# battery-board.net
KiCad netlist of a schematic drawn in EAGLE
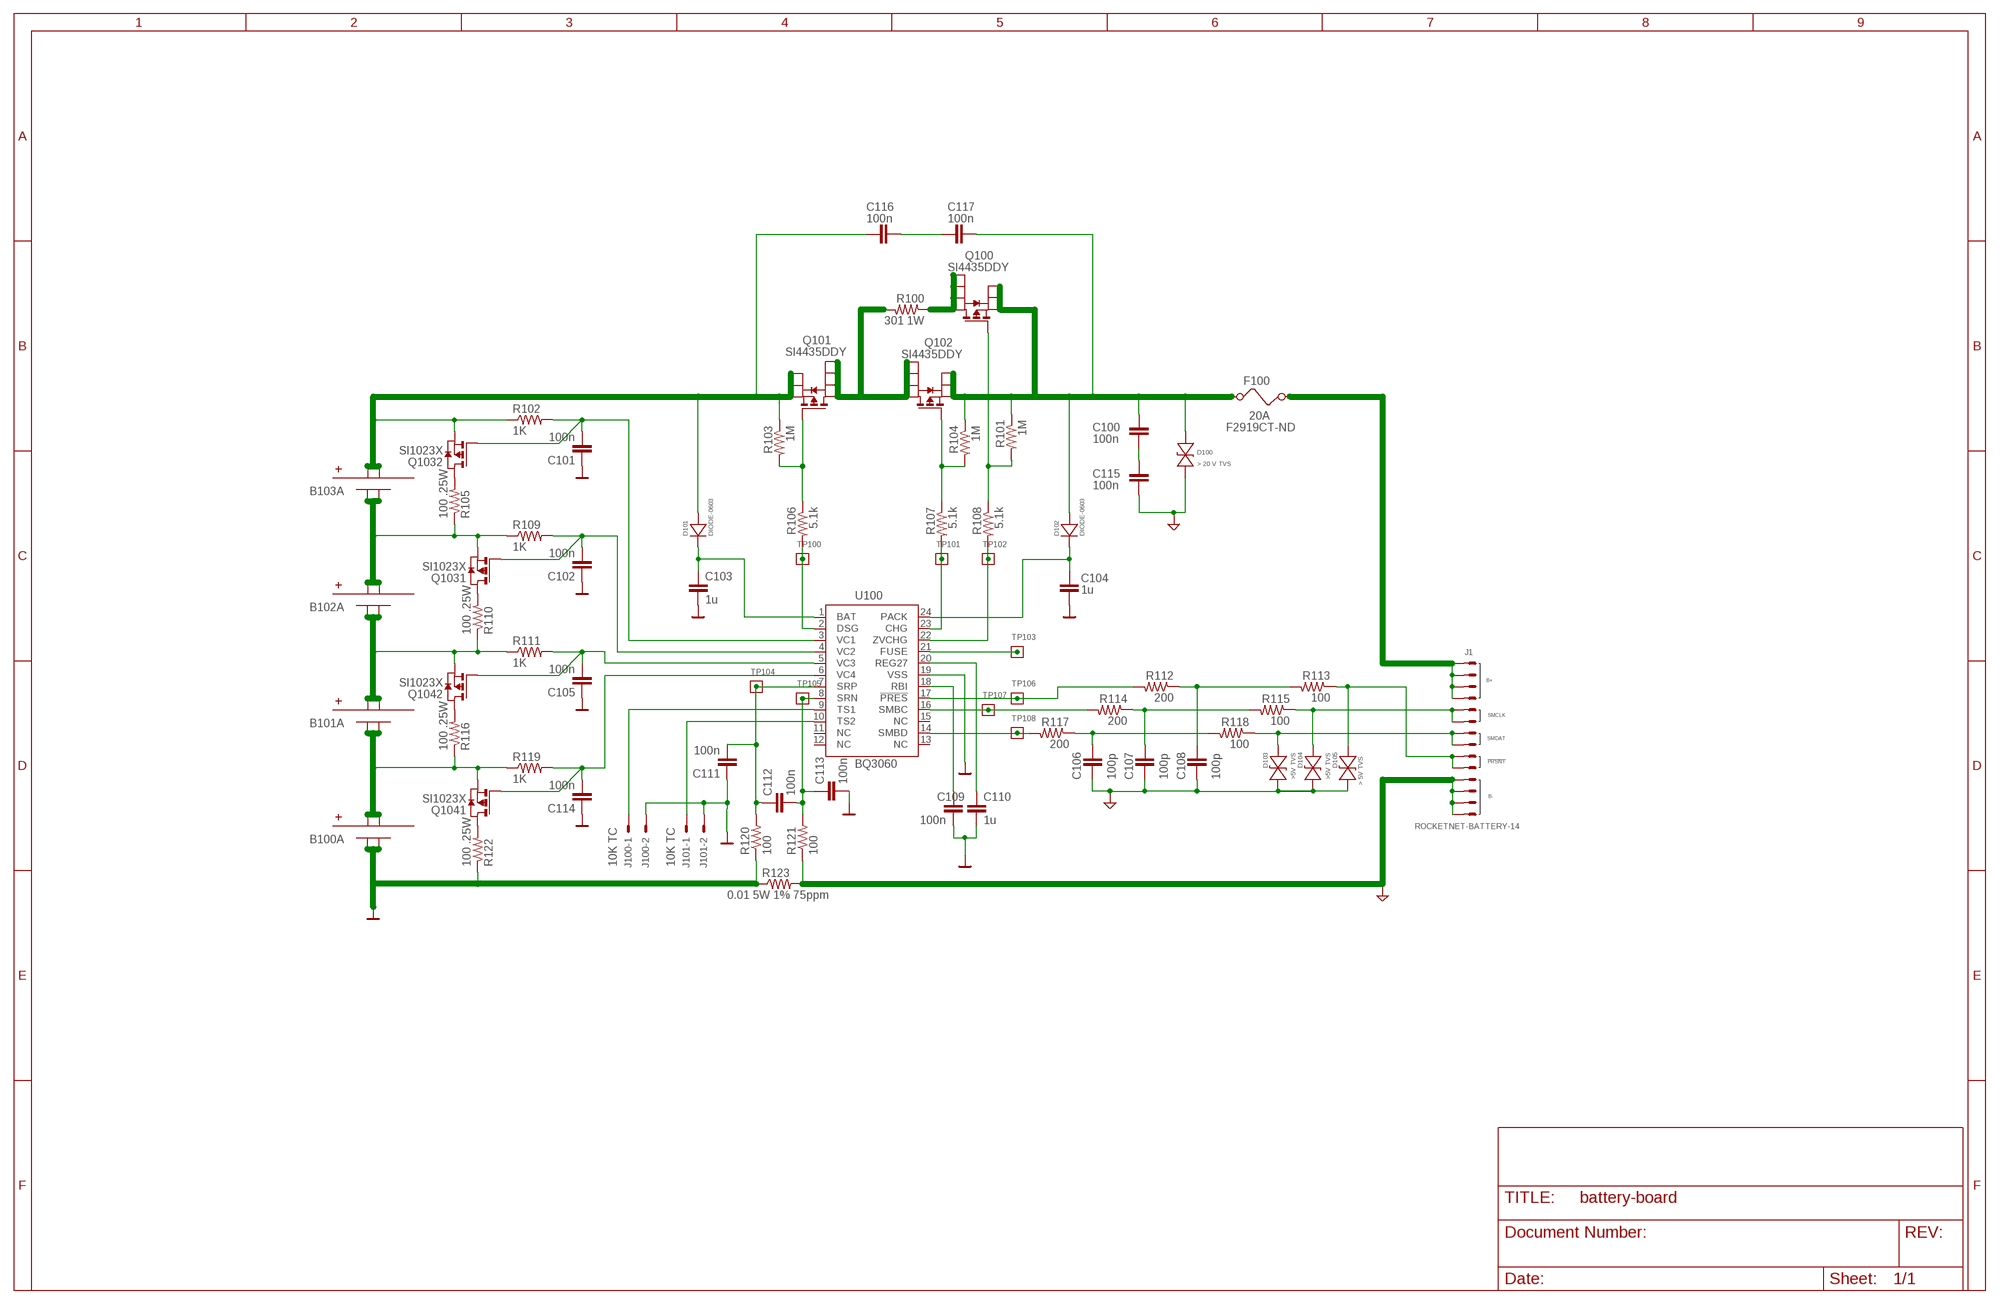
[diagram p0: schematic, sheet 1]

(export (version "E")
  (design (tool "Eeschema 10.0.6"))
  (components
    (comp (ref "B100A")
      (value "LIPO-8AHR")
      (footprint "eagle-import:LIPO-8AHR-PAC")
      (libsource (lib "eagle-import") (part "LIPO-8AHR"))
    )
    (comp (ref "B101A")
      (value "LIPO-8AHR")
      (footprint "eagle-import:LIPO-8AHR-PAC")
      (libsource (lib "eagle-import") (part "LIPO-8AHR"))
    )
    (comp (ref "B102A")
      (value "LIPO-8AHR")
      (footprint "eagle-import:LIPO-8AHR-PAC")
      (libsource (lib "eagle-import") (part "LIPO-8AHR"))
    )
    (comp (ref "B103A")
      (value "LIPO-8AHR")
      (footprint "eagle-import:LIPO-8AHR-PAC")
      (libsource (lib "eagle-import") (part "LIPO-8AHR"))
    )
    (comp (ref "C100")
      (value "100n")
      (footprint "eagle-import:0603-B-NOSILK")
      (libsource (lib "eagle-import") (part "C-EU0603-B-NOSILK"))
    )
    (comp (ref "C101")
      (value "100n")
      (footprint "eagle-import:0402-B-NOSILK")
      (libsource (lib "eagle-import") (part "C-EU0402-B-NOSILK"))
    )
    (comp (ref "C102")
      (value "100n")
      (footprint "eagle-import:0402-B-NOSILK")
      (libsource (lib "eagle-import") (part "C-EU0402-B-NOSILK"))
    )
    (comp (ref "C103")
      (value "1u")
      (footprint "eagle-import:0603-B-NOSILK")
      (libsource (lib "eagle-import") (part "C-EU0603-B-NOSILK"))
    )
    (comp (ref "C104")
      (value "1u")
      (footprint "eagle-import:0603-B-NOSILK")
      (libsource (lib "eagle-import") (part "C-EU0603-B-NOSILK"))
    )
    (comp (ref "C105")
      (value "100n")
      (footprint "eagle-import:0402-B-NOSILK")
      (libsource (lib "eagle-import") (part "C-EU0402-B-NOSILK"))
    )
    (comp (ref "C106")
      (value "100p")
      (footprint "eagle-import:0603-B-NOSILK")
      (libsource (lib "eagle-import") (part "C-EU0603-B-NOSILK"))
    )
    (comp (ref "C107")
      (value "100p")
      (footprint "eagle-import:0603-B-NOSILK")
      (libsource (lib "eagle-import") (part "C-EU0603-B-NOSILK"))
    )
    (comp (ref "C108")
      (value "100p")
      (footprint "eagle-import:0603-B-NOSILK")
      (libsource (lib "eagle-import") (part "C-EU0603-B-NOSILK"))
    )
    (comp (ref "C109")
      (value "100n")
      (footprint "eagle-import:0402-B-NOSILK")
      (libsource (lib "eagle-import") (part "C-EU0402-B-NOSILK"))
    )
    (comp (ref "C110")
      (value "1u")
      (footprint "eagle-import:0603-B-NOSILK")
      (libsource (lib "eagle-import") (part "C-EU0603-B-NOSILK"))
    )
    (comp (ref "C111")
      (value "100n")
      (footprint "eagle-import:0402-B-NOSILK")
      (libsource (lib "eagle-import") (part "C-EU0402-B-NOSILK"))
    )
    (comp (ref "C112")
      (value "100n")
      (footprint "eagle-import:0402-B-NOSILK")
      (libsource (lib "eagle-import") (part "C-EU0402-B-NOSILK"))
    )
    (comp (ref "C113")
      (value "100n")
      (footprint "eagle-import:0402-B-NOSILK")
      (libsource (lib "eagle-import") (part "C-EU0402-B-NOSILK"))
    )
    (comp (ref "C114")
      (value "100n")
      (footprint "eagle-import:0402-B-NOSILK")
      (libsource (lib "eagle-import") (part "C-EU0402-B-NOSILK"))
    )
    (comp (ref "C115")
      (value "100n")
      (footprint "eagle-import:0603-B-NOSILK")
      (libsource (lib "eagle-import") (part "C-EU0603-B-NOSILK"))
    )
    (comp (ref "C116")
      (value "100n")
      (footprint "eagle-import:0603-B-NOSILK")
      (libsource (lib "eagle-import") (part "C-EU0603-B-NOSILK"))
    )
    (comp (ref "C117")
      (value "100n")
      (footprint "eagle-import:0603-B-NOSILK")
      (libsource (lib "eagle-import") (part "C-EU0603-B-NOSILK"))
    )
    (comp (ref "D100")
      (value "> 20 V TVS")
      (footprint "eagle-import:0603-B-NOSILK-DIODE")
      (libsource (lib "eagle-import") (part "TVS-0603"))
    )
    (comp (ref "D101")
      (value "DIODE-0603")
      (footprint "eagle-import:0603-B-NOSILK-DIODE")
      (libsource (lib "eagle-import") (part "DIODE-0603"))
    )
    (comp (ref "D102")
      (value "DIODE-0603")
      (footprint "eagle-import:0603-B-NOSILK-DIODE")
      (libsource (lib "eagle-import") (part "DIODE-0603"))
    )
    (comp (ref "D103")
      (value ">5V TVS")
      (footprint "eagle-import:0603-B-NOSILK-DIODE")
      (libsource (lib "eagle-import") (part "TVS-0603"))
    )
    (comp (ref "D104")
      (value ">5V TVS")
      (footprint "eagle-import:0603-B-NOSILK-DIODE")
      (libsource (lib "eagle-import") (part "TVS-0603"))
    )
    (comp (ref "D105")
      (value "> 5V TVS")
      (footprint "eagle-import:0603-B-NOSILK-DIODE")
      (libsource (lib "eagle-import") (part "TVS-0603"))
    )
    (comp (ref "F100")
      (value "20A")
      (footprint "eagle-import:1206")
      (fields (field (name "DK") "F2919CT-ND"))
      (libsource (lib "eagle-import") (part "FUSE1206"))
    )
    (comp (ref "J1")
      (value "ROCKETNET-BATTERY-14")
      (footprint "eagle-import:ROCKETNET-CONNECTOR-M-14")
      (libsource (lib "eagle-import") (part "ROCKETNET-BATTERY-14"))
    )
    (comp (ref "J100")
      (value "87758-0216")
      (footprint "eagle-import:87758-0216")
      (libsource (lib "eagle-import") (part "87758-0216"))
    )
    (comp (ref "J101")
      (value "87758-0216")
      (footprint "eagle-import:87758-0216")
      (libsource (lib "eagle-import") (part "87758-0216"))
    )
    (comp (ref "Q100")
      (value "SI4435DDY")
      (footprint "eagle-import:SO-8")
      (libsource (lib "eagle-import") (part "SI4435DDY"))
    )
    (comp (ref "Q101")
      (value "SI4435DDY")
      (footprint "eagle-import:SO-8")
      (libsource (lib "eagle-import") (part "SI4435DDY"))
    )
    (comp (ref "Q102")
      (value "SI4435DDY")
      (footprint "eagle-import:SO-8")
      (libsource (lib "eagle-import") (part "SI4435DDY"))
    )
    (comp (ref "Q103")
      (value "SI1023X")
      (footprint "eagle-import:SOT-563")
      (libsource (lib "eagle-import") (part "SI1023X"))
    )
    (comp (ref "Q104")
      (value "SI1023X")
      (footprint "eagle-import:SOT-563")
      (libsource (lib "eagle-import") (part "SI1023X"))
    )
    (comp (ref "R100")
      (value "301 1W")
      (footprint "eagle-import:1206-B")
      (libsource (lib "eagle-import") (part "R-US_1206-B"))
    )
    (comp (ref "R101")
      (value "1M")
      (footprint "eagle-import:0402-B-NOSILK")
      (libsource (lib "eagle-import") (part "R-US_0402-B-NOSILK"))
    )
    (comp (ref "R102")
      (value "1K")
      (footprint "eagle-import:0402-B-NOSILK")
      (libsource (lib "eagle-import") (part "R-US_0402-B-NOSILK"))
    )
    (comp (ref "R103")
      (value "1M")
      (footprint "eagle-import:0402-B-NOSILK")
      (libsource (lib "eagle-import") (part "R-US_0402-B-NOSILK"))
    )
    (comp (ref "R104")
      (value "1M")
      (footprint "eagle-import:0402-B-NOSILK")
      (libsource (lib "eagle-import") (part "R-US_0402-B-NOSILK"))
    )
    (comp (ref "R105")
      (value "100 .25W")
      (footprint "eagle-import:0603-B-NOSILK")
      (libsource (lib "eagle-import") (part "R-US_0603-B-NOSILK"))
    )
    (comp (ref "R106")
      (value "5.1k")
      (footprint "eagle-import:0402-B-NOSILK")
      (libsource (lib "eagle-import") (part "R-US_0402-B-NOSILK"))
    )
    (comp (ref "R107")
      (value "5.1k")
      (footprint "eagle-import:0402-B-NOSILK")
      (libsource (lib "eagle-import") (part "R-US_0402-B-NOSILK"))
    )
    (comp (ref "R108")
      (value "5.1k")
      (footprint "eagle-import:0402-B-NOSILK")
      (libsource (lib "eagle-import") (part "R-US_0402-B-NOSILK"))
    )
    (comp (ref "R109")
      (value "1K")
      (footprint "eagle-import:0402-B-NOSILK")
      (libsource (lib "eagle-import") (part "R-US_0402-B-NOSILK"))
    )
    (comp (ref "R110")
      (value "100 .25W")
      (footprint "eagle-import:0603-B-NOSILK")
      (libsource (lib "eagle-import") (part "R-US_0603-B-NOSILK"))
    )
    (comp (ref "R111")
      (value "1K")
      (footprint "eagle-import:0402-B-NOSILK")
      (libsource (lib "eagle-import") (part "R-US_0402-B-NOSILK"))
    )
    (comp (ref "R112")
      (value "200")
      (footprint "eagle-import:0603-B-NOSILK")
      (libsource (lib "eagle-import") (part "R-US_0603-B-NOSILK"))
    )
    (comp (ref "R113")
      (value "100")
      (footprint "eagle-import:0603-B-NOSILK")
      (libsource (lib "eagle-import") (part "R-US_0603-B-NOSILK"))
    )
    (comp (ref "R114")
      (value "200")
      (footprint "eagle-import:0603-B-NOSILK")
      (libsource (lib "eagle-import") (part "R-US_0603-B-NOSILK"))
    )
    (comp (ref "R115")
      (value "100")
      (footprint "eagle-import:0603-B-NOSILK")
      (libsource (lib "eagle-import") (part "R-US_0603-B-NOSILK"))
    )
    (comp (ref "R116")
      (value "100 .25W")
      (footprint "eagle-import:0603-B-NOSILK")
      (libsource (lib "eagle-import") (part "R-US_0603-B-NOSILK"))
    )
    (comp (ref "R117")
      (value "200")
      (footprint "eagle-import:0603-B-NOSILK")
      (libsource (lib "eagle-import") (part "R-US_0603-B-NOSILK"))
    )
    (comp (ref "R118")
      (value "100")
      (footprint "eagle-import:0603-B-NOSILK")
      (libsource (lib "eagle-import") (part "R-US_0603-B-NOSILK"))
    )
    (comp (ref "R119")
      (value "1K")
      (footprint "eagle-import:0402-B-NOSILK")
      (libsource (lib "eagle-import") (part "R-US_0402-B-NOSILK"))
    )
    (comp (ref "R120")
      (value "100")
      (footprint "eagle-import:0402-B-NOSILK")
      (libsource (lib "eagle-import") (part "R-US_0402-B-NOSILK"))
    )
    (comp (ref "R121")
      (value "100")
      (footprint "eagle-import:0402-B-NOSILK")
      (libsource (lib "eagle-import") (part "R-US_0402-B-NOSILK"))
    )
    (comp (ref "R122")
      (value "100 .25W")
      (footprint "eagle-import:0603-B-NOSILK")
      (libsource (lib "eagle-import") (part "R-US_0603-B-NOSILK"))
    )
    (comp (ref "R123")
      (value "0.01 5W 1% 75ppm")
      (footprint "eagle-import:VISHAY-2818")
      (libsource (lib "eagle-import") (part "R-US-2818"))
    )
    (comp (ref "TP100")
      (value "TEST-POINT")
      (footprint "eagle-import:2MM-TEST-POINT")
      (libsource (lib "eagle-import") (part "TEST-POINT"))
    )
    (comp (ref "TP101")
      (value "TEST-POINT")
      (footprint "eagle-import:2MM-TEST-POINT")
      (libsource (lib "eagle-import") (part "TEST-POINT"))
    )
    (comp (ref "TP102")
      (value "TEST-POINT")
      (footprint "eagle-import:2MM-TEST-POINT")
      (libsource (lib "eagle-import") (part "TEST-POINT"))
    )
    (comp (ref "TP103")
      (value "TEST-POINT")
      (footprint "eagle-import:2MM-TEST-POINT")
      (libsource (lib "eagle-import") (part "TEST-POINT"))
    )
    (comp (ref "TP104")
      (value "TEST-POINT")
      (footprint "eagle-import:2MM-TEST-POINT")
      (libsource (lib "eagle-import") (part "TEST-POINT"))
    )
    (comp (ref "TP105")
      (value "TEST-POINT")
      (footprint "eagle-import:2MM-TEST-POINT")
      (libsource (lib "eagle-import") (part "TEST-POINT"))
    )
    (comp (ref "TP106")
      (value "TEST-POINT")
      (footprint "eagle-import:2MM-TEST-POINT")
      (libsource (lib "eagle-import") (part "TEST-POINT"))
    )
    (comp (ref "TP107")
      (value "TEST-POINT")
      (footprint "eagle-import:2MM-TEST-POINT")
      (libsource (lib "eagle-import") (part "TEST-POINT"))
    )
    (comp (ref "TP108")
      (value "TEST-POINT")
      (footprint "eagle-import:2MM-TEST-POINT")
      (libsource (lib "eagle-import") (part "TEST-POINT"))
    )
    (comp (ref "U100")
      (value "BQ3060PW")
      (footprint "eagle-import:PW-R-PDSO-G24")
      (libsource (lib "eagle-import") (part "BQ3060PW"))
    )
  )
  (nets
    (net (code "1") (name "Net-(C100-Pad1)") (class "Default")
      (node (ref "C100") (pin "1") (pinfunction "1_1") (pintype "passive"))
      (node (ref "C117") (pin "2") (pinfunction "2_2") (pintype "passive"))
      (node (ref "D100") (pin "ANODE") (pinfunction "ANODE_ANODE") (pintype "passive"))
      (node (ref "D102") (pin "ANODE") (pinfunction "ANODE_ANODE") (pintype "passive"))
      (node (ref "F100") (pin "1") (pinfunction "1_1") (pintype "passive"))
      (node (ref "Q100") (pin "1") (pinfunction "S_1") (pintype "passive"))
      (node (ref "Q100") (pin "2") (pinfunction "S_2") (pintype "passive"))
      (node (ref "Q100") (pin "3") (pinfunction "S_3") (pintype "passive"))
      (node (ref "Q102") (pin "1") (pinfunction "S_1") (pintype "passive"))
      (node (ref "Q102") (pin "2") (pinfunction "S_2") (pintype "passive"))
      (node (ref "Q102") (pin "3") (pinfunction "S_3") (pintype "passive"))
      (node (ref "R101") (pin "1") (pinfunction "1_1") (pintype "passive"))
      (node (ref "R104") (pin "1") (pinfunction "1_1") (pintype "passive"))
    )
    (net (code "2") (name "Net-(C100-Pad2)") (class "Default")
      (node (ref "C100") (pin "2") (pinfunction "2_2") (pintype "passive"))
      (node (ref "C115") (pin "1") (pinfunction "1_1") (pintype "passive"))
    )
    (net (code "3") (name "Net-(C106-Pad1)") (class "Default")
      (node (ref "C106") (pin "1") (pinfunction "1_1") (pintype "passive"))
      (node (ref "R117") (pin "1") (pinfunction "1_1") (pintype "passive"))
      (node (ref "R118") (pin "2") (pinfunction "2_2") (pintype "passive"))
    )
    (net (code "4") (name "Net-(C107-Pad1)") (class "Default")
      (node (ref "C107") (pin "1") (pinfunction "1_1") (pintype "passive"))
      (node (ref "R114") (pin "1") (pinfunction "1_1") (pintype "passive"))
      (node (ref "R115") (pin "2") (pinfunction "2_2") (pintype "passive"))
    )
    (net (code "5") (name "Net-(C108-Pad1)") (class "Default")
      (node (ref "C108") (pin "1") (pinfunction "1_1") (pintype "passive"))
      (node (ref "R112") (pin "1") (pinfunction "1_1") (pintype "passive"))
      (node (ref "R113") (pin "2") (pinfunction "2_2") (pintype "passive"))
    )
    (net (code "6") (name "Net-(C116-Pad2)") (class "Default")
      (node (ref "C116") (pin "2") (pinfunction "2_2") (pintype "passive"))
      (node (ref "C117") (pin "1") (pinfunction "1_1") (pintype "passive"))
    )
    (net (code "7") (name "Net-(D103-PadANODE)") (class "Default")
      (node (ref "D103") (pin "ANODE") (pinfunction "ANODE_ANODE") (pintype "passive"))
      (node (ref "J1") (pin "SMDAT@7") (pinfunction "SMDAT_SMDAT@7") (pintype "passive"))
      (node (ref "J1") (pin "SMDAT@8") (pinfunction "SMDAT_SMDAT@8") (pintype "passive"))
      (node (ref "R118") (pin "1") (pinfunction "1_1") (pintype "passive"))
    )
    (net (code "8") (name "Net-(D104-PadANODE)") (class "Default")
      (node (ref "D104") (pin "ANODE") (pinfunction "ANODE_ANODE") (pintype "passive"))
      (node (ref "J1") (pin "SMCLK@3") (pinfunction "SMCLK_SMCLK@3") (pintype "passive"))
      (node (ref "J1") (pin "SMCLK@4") (pinfunction "SMCLK_SMCLK@4") (pintype "passive"))
      (node (ref "R115") (pin "1") (pinfunction "1_1") (pintype "passive"))
    )
    (net (code "9") (name "Net-(D105-PadANODE)") (class "Default")
      (node (ref "D105") (pin "ANODE") (pinfunction "ANODE_ANODE") (pintype "passive"))
      (node (ref "J1") (pin "!PRSNT@10") (pinfunction "~{PRSNT}_!PRSNT@10") (pintype "passive"))
      (node (ref "J1") (pin "!PRSNT@9") (pinfunction "~{PRSNT}_!PRSNT@9") (pintype "passive"))
      (node (ref "R113") (pin "1") (pinfunction "1_1") (pintype "passive"))
    )
    (net (code "10") (name "Net-(F100-Pad2)") (class "Default")
      (node (ref "F100") (pin "2") (pinfunction "2_2") (pintype "passive"))
      (node (ref "J1") (pin "B+@1") (pinfunction "B+_B+@1") (pintype "power_in"))
      (node (ref "J1") (pin "B+@2") (pinfunction "B+_B+@2") (pintype "power_in"))
      (node (ref "J1") (pin "B+@3") (pinfunction "B+_B+@3") (pintype "passive"))
      (node (ref "J1") (pin "B+@4") (pinfunction "B+_B+@4") (pintype "passive"))
    )
    (net (code "11") (name "Net-(J100A-S)") (class "Default")
      (node (ref "J100") (pin "1") (pinfunction "S_1") (pintype "passive"))
      (node (ref "U100") (pin "9") (pinfunction "TS1_9") (pintype "input"))
    )
    (net (code "12") (name "Net-(J101A-S)") (class "Default")
      (node (ref "J101") (pin "1") (pinfunction "S_1") (pintype "passive"))
      (node (ref "U100") (pin "10") (pinfunction "TS2_10") (pintype "input"))
    )
    (net (code "13") (name "Net-(Q100-D-Pad5)") (class "Default")
      (node (ref "Q100") (pin "5") (pinfunction "D_5") (pintype "passive"))
      (node (ref "Q100") (pin "6") (pinfunction "D_6") (pintype "passive"))
      (node (ref "Q100") (pin "7") (pinfunction "D_7") (pintype "passive"))
      (node (ref "Q100") (pin "8") (pinfunction "D_8") (pintype "passive"))
      (node (ref "R100") (pin "1") (pinfunction "1_1") (pintype "passive"))
    )
    (net (code "14") (name "Net-(Q100-G)") (class "Default")
      (node (ref "Q100") (pin "4") (pinfunction "G_4") (pintype "passive"))
      (node (ref "R101") (pin "2") (pinfunction "2_2") (pintype "passive"))
      (node (ref "R108") (pin "1") (pinfunction "1_1") (pintype "passive"))
    )
    (net (code "15") (name "Net-(Q101-D-Pad5)") (class "Default")
      (node (ref "Q101") (pin "5") (pinfunction "D_5") (pintype "passive"))
      (node (ref "Q101") (pin "6") (pinfunction "D_6") (pintype "passive"))
      (node (ref "Q101") (pin "7") (pinfunction "D_7") (pintype "passive"))
      (node (ref "Q101") (pin "8") (pinfunction "D_8") (pintype "passive"))
      (node (ref "Q102") (pin "5") (pinfunction "D_5") (pintype "passive"))
      (node (ref "Q102") (pin "6") (pinfunction "D_6") (pintype "passive"))
      (node (ref "Q102") (pin "7") (pinfunction "D_7") (pintype "passive"))
      (node (ref "Q102") (pin "8") (pinfunction "D_8") (pintype "passive"))
      (node (ref "R100") (pin "2") (pinfunction "2_2") (pintype "passive"))
    )
    (net (code "16") (name "Net-(Q101-G)") (class "Default")
      (node (ref "Q101") (pin "4") (pinfunction "G_4") (pintype "passive"))
      (node (ref "R103") (pin "2") (pinfunction "2_2") (pintype "passive"))
      (node (ref "R106") (pin "1") (pinfunction "1_1") (pintype "passive"))
    )
    (net (code "17") (name "Net-(Q102-G)") (class "Default")
      (node (ref "Q102") (pin "4") (pinfunction "G_4") (pintype "passive"))
      (node (ref "R104") (pin "2") (pinfunction "2_2") (pintype "passive"))
      (node (ref "R107") (pin "1") (pinfunction "1_1") (pintype "passive"))
    )
    (net (code "18") (name "Net-(Q103A-D)") (class "Default")
      (node (ref "Q103") (pin "6") (pinfunction "D_6") (pintype "passive"))
      (node (ref "R110") (pin "2") (pinfunction "2_2") (pintype "passive"))
    )
    (net (code "19") (name "Net-(Q103A-G)") (class "Default")
      (node (ref "C102") (pin "2") (pinfunction "2_2") (pintype "passive"))
      (node (ref "Q103") (pin "2") (pinfunction "G_2") (pintype "passive"))
      (node (ref "R109") (pin "2") (pinfunction "2_2") (pintype "passive"))
      (node (ref "U100") (pin "4") (pinfunction "VC2_4") (pintype "input"))
    )
    (net (code "20") (name "Net-(Q103A-S)") (class "Default")
      (node (ref "B102A") (pin "B+@1") (pinfunction "B+_B+@1") (pintype "passive"))
      (node (ref "B102A") (pin "B+@2") (pinfunction "B+_B+@2") (pintype "passive"))
      (node (ref "B103A") (pin "B-@1") (pinfunction "B-_B-@1") (pintype "passive"))
      (node (ref "B103A") (pin "B-@2") (pinfunction "B-_B-@2") (pintype "passive"))
      (node (ref "Q103") (pin "1") (pinfunction "S_1") (pintype "passive"))
      (node (ref "R105") (pin "1") (pinfunction "1_1") (pintype "passive"))
      (node (ref "R109") (pin "1") (pinfunction "1_1") (pintype "passive"))
    )
    (net (code "21") (name "Net-(Q103B-D)") (class "Default")
      (node (ref "Q103") (pin "3") (pinfunction "D_3") (pintype "passive"))
      (node (ref "R105") (pin "2") (pinfunction "2_2") (pintype "passive"))
    )
    (net (code "22") (name "Net-(Q103B-G)") (class "Default")
      (node (ref "C101") (pin "2") (pinfunction "2_2") (pintype "passive"))
      (node (ref "Q103") (pin "5") (pinfunction "G_5") (pintype "passive"))
      (node (ref "R102") (pin "2") (pinfunction "2_2") (pintype "passive"))
      (node (ref "U100") (pin "3") (pinfunction "VC1_3") (pintype "input"))
    )
    (net (code "23") (name "Net-(Q103B-S)") (class "Default")
      (node (ref "B103A") (pin "B+@1") (pinfunction "B+_B+@1") (pintype "passive"))
      (node (ref "B103A") (pin "B+@2") (pinfunction "B+_B+@2") (pintype "passive"))
      (node (ref "C116") (pin "1") (pinfunction "1_1") (pintype "passive"))
      (node (ref "D101") (pin "ANODE") (pinfunction "ANODE_ANODE") (pintype "passive"))
      (node (ref "Q101") (pin "1") (pinfunction "S_1") (pintype "passive"))
      (node (ref "Q101") (pin "2") (pinfunction "S_2") (pintype "passive"))
      (node (ref "Q101") (pin "3") (pinfunction "S_3") (pintype "passive"))
      (node (ref "Q103") (pin "4") (pinfunction "S_4") (pintype "passive"))
      (node (ref "R102") (pin "1") (pinfunction "1_1") (pintype "passive"))
      (node (ref "R103") (pin "1") (pinfunction "1_1") (pintype "passive"))
    )
    (net (code "24") (name "Net-(Q104A-D)") (class "Default")
      (node (ref "Q104") (pin "6") (pinfunction "D_6") (pintype "passive"))
      (node (ref "R122") (pin "2") (pinfunction "2_2") (pintype "passive"))
    )
    (net (code "25") (name "Net-(Q104A-G)") (class "Default")
      (node (ref "C114") (pin "2") (pinfunction "2_2") (pintype "passive"))
      (node (ref "Q104") (pin "2") (pinfunction "G_2") (pintype "passive"))
      (node (ref "R119") (pin "2") (pinfunction "2_2") (pintype "passive"))
      (node (ref "U100") (pin "6") (pinfunction "VC4_6") (pintype "input"))
    )
    (net (code "26") (name "Net-(Q104A-S)") (class "Default")
      (node (ref "B100A") (pin "B+@1") (pinfunction "B+_B+@1") (pintype "passive"))
      (node (ref "B100A") (pin "B+@2") (pinfunction "B+_B+@2") (pintype "passive"))
      (node (ref "B101A") (pin "B-@1") (pinfunction "B-_B-@1") (pintype "passive"))
      (node (ref "B101A") (pin "B-@2") (pinfunction "B-_B-@2") (pintype "passive"))
      (node (ref "Q104") (pin "1") (pinfunction "S_1") (pintype "passive"))
      (node (ref "R116") (pin "1") (pinfunction "1_1") (pintype "passive"))
      (node (ref "R119") (pin "1") (pinfunction "1_1") (pintype "passive"))
    )
    (net (code "27") (name "Net-(Q104B-D)") (class "Default")
      (node (ref "Q104") (pin "3") (pinfunction "D_3") (pintype "passive"))
      (node (ref "R116") (pin "2") (pinfunction "2_2") (pintype "passive"))
    )
    (net (code "28") (name "Net-(Q104B-G)") (class "Default")
      (node (ref "C105") (pin "2") (pinfunction "2_2") (pintype "passive"))
      (node (ref "Q104") (pin "5") (pinfunction "G_5") (pintype "passive"))
      (node (ref "R111") (pin "2") (pinfunction "2_2") (pintype "passive"))
      (node (ref "U100") (pin "5") (pinfunction "VC3_5") (pintype "input"))
    )
    (net (code "29") (name "Net-(Q104B-S)") (class "Default")
      (node (ref "B101A") (pin "B+@1") (pinfunction "B+_B+@1") (pintype "passive"))
      (node (ref "B101A") (pin "B+@2") (pinfunction "B+_B+@2") (pintype "passive"))
      (node (ref "B102A") (pin "B-@1") (pinfunction "B-_B-@1") (pintype "passive"))
      (node (ref "B102A") (pin "B-@2") (pinfunction "B-_B-@2") (pintype "passive"))
      (node (ref "Q104") (pin "4") (pinfunction "S_4") (pintype "passive"))
      (node (ref "R110") (pin "1") (pinfunction "1_1") (pintype "passive"))
      (node (ref "R111") (pin "1") (pinfunction "1_1") (pintype "passive"))
    )
    (net (code "30") (name "Net-(TP100-P$1)") (class "Default")
      (node (ref "R106") (pin "2") (pinfunction "2_2") (pintype "passive"))
      (node (ref "TP100") (pin "1") (pinfunction "P$1_1") (pintype "passive"))
      (node (ref "U100") (pin "2") (pinfunction "DSG_2") (pintype "output"))
    )
    (net (code "31") (name "Net-(TP101-P$1)") (class "Default")
      (node (ref "R107") (pin "2") (pinfunction "2_2") (pintype "passive"))
      (node (ref "TP101") (pin "1") (pinfunction "P$1_1") (pintype "passive"))
      (node (ref "U100") (pin "23") (pinfunction "CHG_23") (pintype "output"))
    )
    (net (code "32") (name "Net-(TP102-P$1)") (class "Default")
      (node (ref "R108") (pin "2") (pinfunction "2_2") (pintype "passive"))
      (node (ref "TP102") (pin "1") (pinfunction "P$1_1") (pintype "passive"))
      (node (ref "U100") (pin "22") (pinfunction "ZVCHG_22") (pintype "output"))
    )
    (net (code "33") (name "Net-(TP103-P$1)") (class "Default")
      (node (ref "TP103") (pin "1") (pinfunction "P$1_1") (pintype "passive"))
      (node (ref "U100") (pin "21") (pinfunction "FUSE_21") (pintype "bidirectional"))
    )
    (net (code "34") (name "Net-(TP104-P$1)") (class "Default")
      (node (ref "C111") (pin "2") (pinfunction "2_2") (pintype "passive"))
      (node (ref "C112") (pin "1") (pinfunction "1_1") (pintype "passive"))
      (node (ref "R120") (pin "2") (pinfunction "2_2") (pintype "passive"))
      (node (ref "TP104") (pin "1") (pinfunction "P$1_1") (pintype "passive"))
      (node (ref "U100") (pin "7") (pinfunction "SRP_7") (pintype "input"))
    )
    (net (code "35") (name "Net-(TP105-P$1)") (class "Default")
      (node (ref "C112") (pin "2") (pinfunction "2_2") (pintype "passive"))
      (node (ref "C113") (pin "1") (pinfunction "1_1") (pintype "passive"))
      (node (ref "R121") (pin "2") (pinfunction "2_2") (pintype "passive"))
      (node (ref "TP105") (pin "1") (pinfunction "P$1_1") (pintype "passive"))
      (node (ref "U100") (pin "8") (pinfunction "SRN_8") (pintype "input"))
    )
    (net (code "36") (name "Net-(TP106-P$1)") (class "Default")
      (node (ref "R112") (pin "2") (pinfunction "2_2") (pintype "passive"))
      (node (ref "TP106") (pin "1") (pinfunction "P$1_1") (pintype "passive"))
      (node (ref "U100") (pin "17") (pinfunction "~{PRES}_17") (pintype "input"))
    )
    (net (code "37") (name "Net-(TP107-P$1)") (class "Default")
      (node (ref "R114") (pin "2") (pinfunction "2_2") (pintype "passive"))
      (node (ref "TP107") (pin "1") (pinfunction "P$1_1") (pintype "passive"))
      (node (ref "U100") (pin "16") (pinfunction "SMBC_16") (pintype "bidirectional"))
    )
    (net (code "38") (name "Net-(TP108-P$1)") (class "Default")
      (node (ref "R117") (pin "2") (pinfunction "2_2") (pintype "passive"))
      (node (ref "TP108") (pin "1") (pinfunction "P$1_1") (pintype "passive"))
      (node (ref "U100") (pin "14") (pinfunction "SMBD_14") (pintype "bidirectional"))
    )
    (net (code "39") (name "Net-(U100-BAT)") (class "Default")
      (node (ref "C103") (pin "1") (pinfunction "1_1") (pintype "passive"))
      (node (ref "D101") (pin "CATHODE") (pinfunction "CATHODE_CATHODE") (pintype "passive"))
      (node (ref "U100") (pin "1") (pinfunction "BAT_1") (pintype "power_in"))
    )
    (net (code "40") (name "Net-(U100-PACK)") (class "Default")
      (node (ref "C104") (pin "1") (pinfunction "1_1") (pintype "passive"))
      (node (ref "D102") (pin "CATHODE") (pinfunction "CATHODE_CATHODE") (pintype "passive"))
      (node (ref "U100") (pin "24") (pinfunction "PACK_24") (pintype "power_in"))
    )
    (net (code "41") (name "Net-(U100-RBI)") (class "Default")
      (node (ref "C109") (pin "1") (pinfunction "1_1") (pintype "passive"))
      (node (ref "U100") (pin "18") (pinfunction "RBI_18") (pintype "power_in"))
    )
    (net (code "42") (name "Net-(U100-REG27)") (class "Default")
      (node (ref "C110") (pin "1") (pinfunction "1_1") (pintype "passive"))
      (node (ref "U100") (pin "20") (pinfunction "REG27_20") (pintype "power_in"))
    )
    (net (code "43") (name "SUP_GND_BAR") (class "Default")
      (node (ref "B100A") (pin "B-@1") (pinfunction "B-_B-@1") (pintype "passive"))
      (node (ref "B100A") (pin "B-@2") (pinfunction "B-_B-@2") (pintype "passive"))
      (node (ref "C101") (pin "1") (pinfunction "1_1") (pintype "passive"))
      (node (ref "C102") (pin "1") (pinfunction "1_1") (pintype "passive"))
      (node (ref "C103") (pin "2") (pinfunction "2_2") (pintype "passive"))
      (node (ref "C104") (pin "2") (pinfunction "2_2") (pintype "passive"))
      (node (ref "C105") (pin "1") (pinfunction "1_1") (pintype "passive"))
      (node (ref "C109") (pin "2") (pinfunction "2_2") (pintype "passive"))
      (node (ref "C110") (pin "2") (pinfunction "2_2") (pintype "passive"))
      (node (ref "C111") (pin "1") (pinfunction "1_1") (pintype "passive"))
      (node (ref "C113") (pin "2") (pinfunction "2_2") (pintype "passive"))
      (node (ref "C114") (pin "1") (pinfunction "1_1") (pintype "passive"))
      (node (ref "J100") (pin "2") (pinfunction "S_2") (pintype "passive"))
      (node (ref "J101") (pin "2") (pinfunction "S_2") (pintype "passive"))
      (node (ref "R120") (pin "1") (pinfunction "1_1") (pintype "passive"))
      (node (ref "R122") (pin "1") (pinfunction "1_1") (pintype "passive"))
      (node (ref "R123") (pin "P$1") (pinfunction "1_P$1") (pintype "passive"))
      (node (ref "U100") (pin "19") (pinfunction "VSS_19") (pintype "power_in"))
    )
    (net (code "44") (name "SUP_GND_TRIANGLE") (class "Default")
      (node (ref "C106") (pin "2") (pinfunction "2_2") (pintype "passive"))
      (node (ref "C107") (pin "2") (pinfunction "2_2") (pintype "passive"))
      (node (ref "C108") (pin "2") (pinfunction "2_2") (pintype "passive"))
      (node (ref "C115") (pin "2") (pinfunction "2_2") (pintype "passive"))
      (node (ref "D100") (pin "CATHODE") (pinfunction "CATHODE_CATHODE") (pintype "passive"))
      (node (ref "D103") (pin "CATHODE") (pinfunction "CATHODE_CATHODE") (pintype "passive"))
      (node (ref "D104") (pin "CATHODE") (pinfunction "CATHODE_CATHODE") (pintype "passive"))
      (node (ref "D105") (pin "CATHODE") (pinfunction "CATHODE_CATHODE") (pintype "passive"))
      (node (ref "J1") (pin "B-@11") (pinfunction "B-_B-@11") (pintype "passive"))
      (node (ref "J1") (pin "B-@12") (pinfunction "B-_B-@12") (pintype "passive"))
      (node (ref "J1") (pin "B-@13") (pinfunction "B-_B-@13") (pintype "passive"))
      (node (ref "J1") (pin "B-@14") (pinfunction "B-_B-@14") (pintype "passive"))
      (node (ref "R121") (pin "1") (pinfunction "1_1") (pintype "passive"))
      (node (ref "R123") (pin "P$2") (pinfunction "2_P$2") (pintype "passive"))
    )
    (net (code "45") (name "unconnected-(U100-NC-Pad11)") (class "Default")
      (node (ref "U100") (pin "11") (pinfunction "NC_11") (pintype "no_connect"))
    )
    (net (code "46") (name "unconnected-(U100-NC-Pad12)") (class "Default")
      (node (ref "U100") (pin "12") (pinfunction "NC_12") (pintype "no_connect"))
    )
    (net (code "47") (name "unconnected-(U100-NC-Pad13)") (class "Default")
      (node (ref "U100") (pin "13") (pinfunction "NC_13") (pintype "no_connect"))
    )
    (net (code "48") (name "unconnected-(U100-NC-Pad15)") (class "Default")
      (node (ref "U100") (pin "15") (pinfunction "NC_15") (pintype "no_connect"))
    )
  )
)
